# Sheet1.net
KiCad netlist of a schematic drawn in Altium Designer
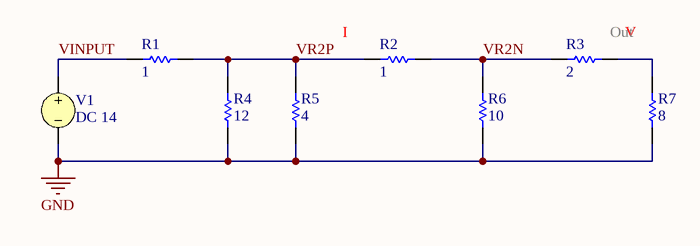
[diagram p0: Sheet1.SchDoc]

(export (version "E")
  (design (tool "Eeschema 10.0.6"))
  (components
    (comp (ref "R1")
      (value "1")
      (description "Resistor")
      (libsource (lib "Simulation Generic Components") (part "Resistor"))
    )
    (comp (ref "R2")
      (value "1")
      (description "Resistor")
      (libsource (lib "Simulation Generic Components") (part "Resistor"))
    )
    (comp (ref "R3")
      (value "2")
      (description "Resistor")
      (libsource (lib "Simulation Generic Components") (part "Resistor"))
    )
    (comp (ref "R4")
      (value "12")
      (description "Resistor")
      (libsource (lib "Simulation Generic Components") (part "Resistor"))
    )
    (comp (ref "R5")
      (value "4")
      (description "Resistor")
      (libsource (lib "Simulation Generic Components") (part "Resistor"))
    )
    (comp (ref "R6")
      (value "10")
      (description "Resistor")
      (libsource (lib "Simulation Generic Components") (part "Resistor"))
    )
    (comp (ref "R7")
      (value "8")
      (description "Resistor")
      (libsource (lib "Simulation Generic Components") (part "Resistor"))
    )
    (comp (ref "V1")
      (value "DC 14")
      (description "Voltage Source")
      (fields (field (name "PUBLISHER") "Altium Limited"))
      (libsource (lib "Simulation Generic Components") (part "VSRC"))
    )
  )
  (nets
    (net (code "1") (name "/VINPUT") (class "Default")
      (node (ref "R1") (pin "1") (pinfunction "1_1") (pintype "passive"))
      (node (ref "V1") (pin "1") (pinfunction "1_1") (pintype "passive"))
    )
    (net (code "2") (name "/VR2N") (class "Default")
      (node (ref "R2") (pin "1") (pinfunction "1_1") (pintype "passive"))
      (node (ref "R3") (pin "1") (pinfunction "1_1") (pintype "passive"))
      (node (ref "R6") (pin "1") (pinfunction "1_1") (pintype "passive"))
    )
    (net (code "3") (name "/VR2P") (class "Default")
      (node (ref "R1") (pin "2") (pinfunction "2_2") (pintype "passive"))
      (node (ref "R2") (pin "2") (pinfunction "2_2") (pintype "passive"))
      (node (ref "R4") (pin "2") (pinfunction "2_2") (pintype "passive"))
      (node (ref "R5") (pin "2") (pinfunction "2_2") (pintype "passive"))
    )
    (net (code "4") (name "GND") (class "Default")
      (node (ref "R4") (pin "1") (pinfunction "1_1") (pintype "passive"))
      (node (ref "R5") (pin "1") (pinfunction "1_1") (pintype "passive"))
      (node (ref "R6") (pin "2") (pinfunction "2_2") (pintype "passive"))
      (node (ref "R7") (pin "1") (pinfunction "1_1") (pintype "passive"))
      (node (ref "V1") (pin "2") (pinfunction "2_2") (pintype "passive"))
    )
    (net (code "5") (name "Net-(R3-Pad2)") (class "Default")
      (node (ref "R3") (pin "2") (pinfunction "2_2") (pintype "passive"))
      (node (ref "R7") (pin "2") (pinfunction "2_2") (pintype "passive"))
    )
  )
)
